# boardv1.net
KiCad netlist of a schematic drawn in EAGLE
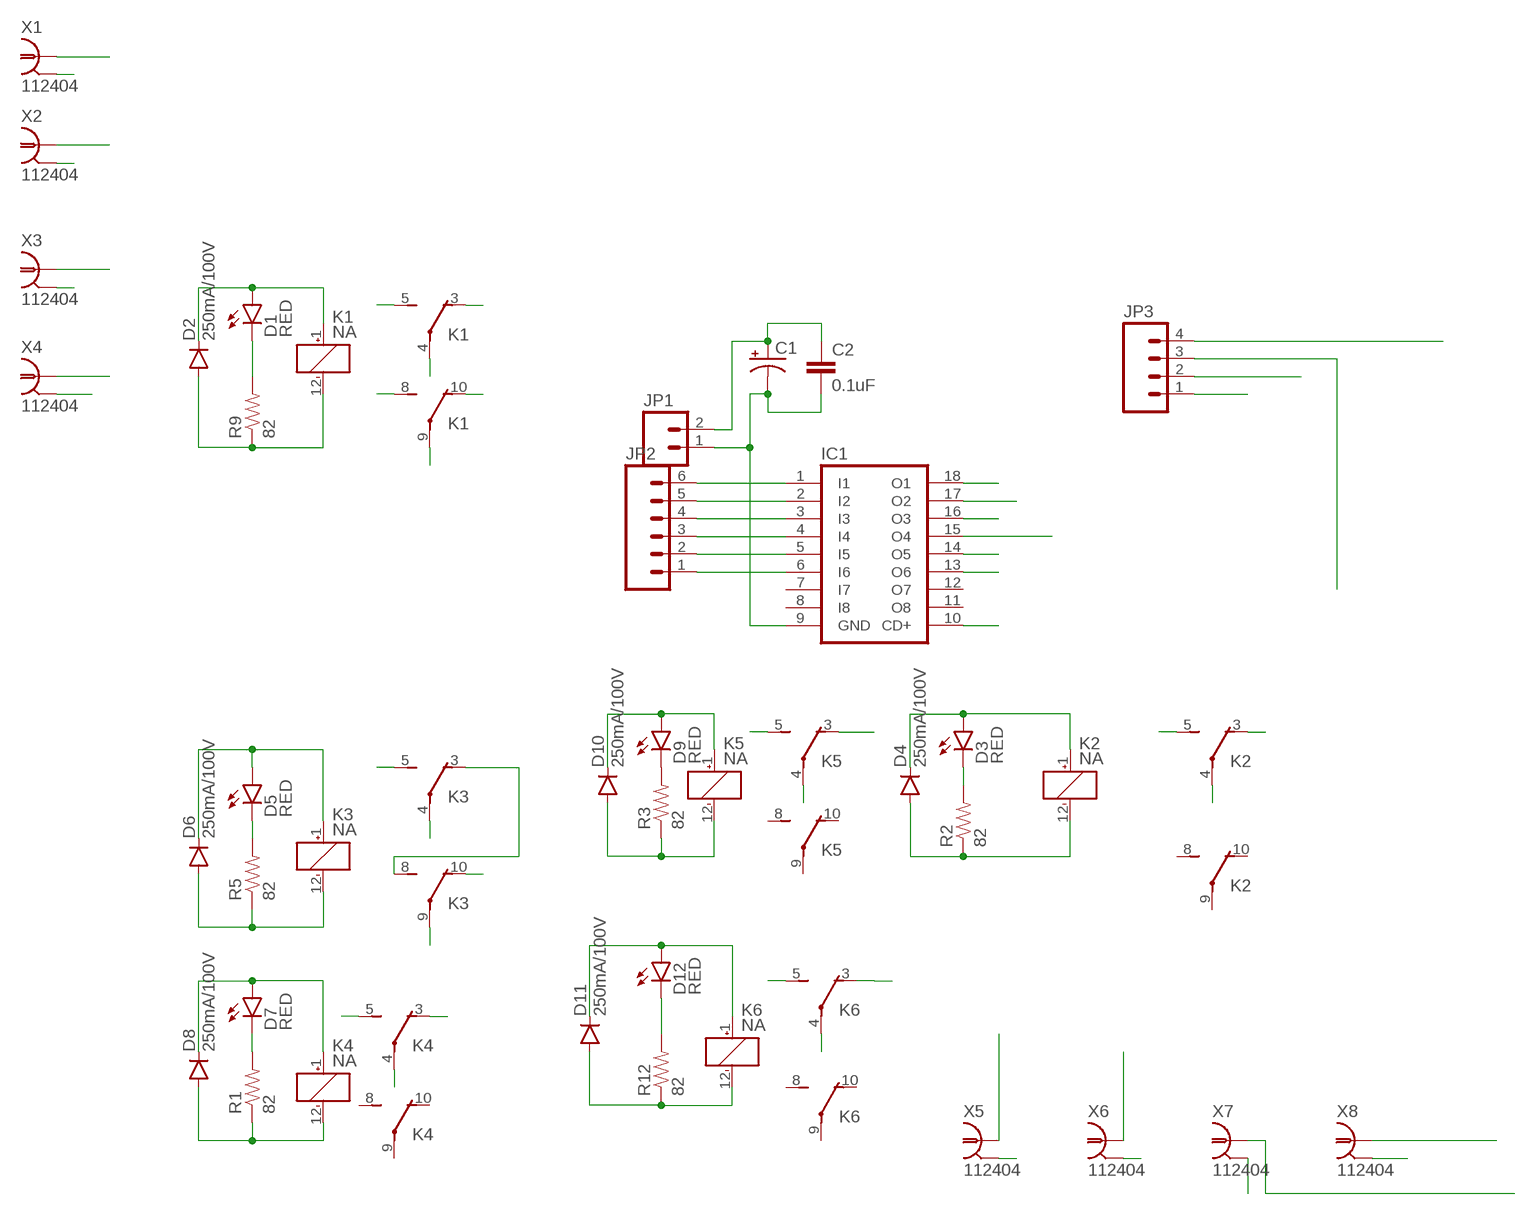
[diagram p0: schematic, sheet 1]

(export (version "E")
  (design (tool "Eeschema 10.0.6"))
  (components
    (comp (ref "C1")
      (value "100UF-25V-20%(PTH)")
      (footprint "eagle-import:CPOL-RADIAL-100UF-25V")
      (libsource (lib "eagle-import") (part "100UF-25V-20%(PTH)"))
    )
    (comp (ref "C2")
      (value "0.1uF")
      (footprint "eagle-import:0603-CAP")
      (libsource (lib "eagle-import") (part "0.1UF-25V-5%(0603)"))
    )
    (comp (ref "D1")
      (value "RED")
      (footprint "eagle-import:LED-1206")
      (libsource (lib "eagle-import") (part "LED-RED1206"))
    )
    (comp (ref "D2")
      (value "250mA/100V")
      (footprint "eagle-import:SOD-323")
      (libsource (lib "eagle-import") (part "DIODEBAS16"))
    )
    (comp (ref "D3")
      (value "RED")
      (footprint "eagle-import:LED-1206")
      (libsource (lib "eagle-import") (part "LED-RED1206"))
    )
    (comp (ref "D4")
      (value "250mA/100V")
      (footprint "eagle-import:SOD-323")
      (libsource (lib "eagle-import") (part "DIODEBAS16"))
    )
    (comp (ref "D5")
      (value "RED")
      (footprint "eagle-import:LED-1206")
      (libsource (lib "eagle-import") (part "LED-RED1206"))
    )
    (comp (ref "D6")
      (value "250mA/100V")
      (footprint "eagle-import:SOD-323")
      (libsource (lib "eagle-import") (part "DIODEBAS16"))
    )
    (comp (ref "D7")
      (value "RED")
      (footprint "eagle-import:LED-1206")
      (libsource (lib "eagle-import") (part "LED-RED1206"))
    )
    (comp (ref "D8")
      (value "250mA/100V")
      (footprint "eagle-import:SOD-323")
      (libsource (lib "eagle-import") (part "DIODEBAS16"))
    )
    (comp (ref "D9")
      (value "RED")
      (footprint "eagle-import:LED-1206")
      (libsource (lib "eagle-import") (part "LED-RED1206"))
    )
    (comp (ref "D10")
      (value "250mA/100V")
      (footprint "eagle-import:SOD-323")
      (libsource (lib "eagle-import") (part "DIODEBAS16"))
    )
    (comp (ref "D11")
      (value "250mA/100V")
      (footprint "eagle-import:SOD-323")
      (libsource (lib "eagle-import") (part "DIODEBAS16"))
    )
    (comp (ref "D12")
      (value "RED")
      (footprint "eagle-import:LED-1206")
      (libsource (lib "eagle-import") (part "LED-RED1206"))
    )
    (comp (ref "IC1")
      (value "ULN2803A")
      (footprint "eagle-import:DIL18")
      (libsource (lib "eagle-import") (part "ULN2803A"))
    )
    (comp (ref "JP1")
      (value "M02PTH")
      (footprint "eagle-import:1X02")
      (libsource (lib "eagle-import") (part "M02PTH"))
    )
    (comp (ref "JP2")
      (value "M06NO_SILK_YES_STOP")
      (footprint "eagle-import:1X06_NO_SILK_YES_STOP")
      (libsource (lib "eagle-import") (part "M06NO_SILK_YES_STOP"))
    )
    (comp (ref "JP3")
      (value "M04PTH")
      (footprint "eagle-import:1X04")
      (libsource (lib "eagle-import") (part "M04PTH"))
    )
    (comp (ref "K1") (value "NA") (footprint "eagle-import:NA") (libsource (lib "eagle-import") (part "NA")))
    (comp (ref "K2") (value "NA") (footprint "eagle-import:NA") (libsource (lib "eagle-import") (part "NA")))
    (comp (ref "K3") (value "NA") (footprint "eagle-import:NA") (libsource (lib "eagle-import") (part "NA")))
    (comp (ref "K4") (value "NA") (footprint "eagle-import:NA") (libsource (lib "eagle-import") (part "NA")))
    (comp (ref "K5") (value "NA") (footprint "eagle-import:NA") (libsource (lib "eagle-import") (part "NA")))
    (comp (ref "K6") (value "NA") (footprint "eagle-import:NA") (libsource (lib "eagle-import") (part "NA")))
    (comp (ref "R1")
      (value "82")
      (footprint "eagle-import:0603-RES")
      (libsource (lib "eagle-import") (part "82OHM-1/10W-1%(0603)SMD"))
    )
    (comp (ref "R2")
      (value "82")
      (footprint "eagle-import:0603-RES")
      (libsource (lib "eagle-import") (part "82OHM-1/10W-1%(0603)SMD"))
    )
    (comp (ref "R3")
      (value "82")
      (footprint "eagle-import:0603-RES")
      (libsource (lib "eagle-import") (part "82OHM-1/10W-1%(0603)SMD"))
    )
    (comp (ref "R5")
      (value "82")
      (footprint "eagle-import:0603-RES")
      (libsource (lib "eagle-import") (part "82OHM-1/10W-1%(0603)SMD"))
    )
    (comp (ref "R9")
      (value "82")
      (footprint "eagle-import:0603-RES")
      (libsource (lib "eagle-import") (part "82OHM-1/10W-1%(0603)SMD"))
    )
    (comp (ref "R12")
      (value "82")
      (footprint "eagle-import:0603-RES")
      (libsource (lib "eagle-import") (part "82OHM-1/10W-1%(0603)SMD"))
    )
    (comp (ref "X1")
      (value "112404")
      (footprint "eagle-import:112404")
      (fields (field (name "MF") "Amphenol Connex"))
      (libsource (lib "eagle-import") (part "112404"))
    )
    (comp (ref "X2")
      (value "112404")
      (footprint "eagle-import:112404")
      (fields (field (name "MF") "Amphenol Connex"))
      (libsource (lib "eagle-import") (part "112404"))
    )
    (comp (ref "X3")
      (value "112404")
      (footprint "eagle-import:112404")
      (fields (field (name "MF") "Amphenol Connex"))
      (libsource (lib "eagle-import") (part "112404"))
    )
    (comp (ref "X4")
      (value "112404")
      (footprint "eagle-import:112404")
      (fields (field (name "MF") "Amphenol Connex"))
      (libsource (lib "eagle-import") (part "112404"))
    )
    (comp (ref "X5")
      (value "112404")
      (footprint "eagle-import:112404")
      (fields (field (name "MF") "Amphenol Connex"))
      (libsource (lib "eagle-import") (part "112404"))
    )
    (comp (ref "X6")
      (value "112404")
      (footprint "eagle-import:112404")
      (fields (field (name "MF") "Amphenol Connex"))
      (libsource (lib "eagle-import") (part "112404"))
    )
    (comp (ref "X7")
      (value "112404")
      (footprint "eagle-import:112404")
      (fields (field (name "MF") "Amphenol Connex"))
      (libsource (lib "eagle-import") (part "112404"))
    )
    (comp (ref "X8")
      (value "112404")
      (footprint "eagle-import:112404")
      (fields (field (name "MF") "Amphenol Connex"))
      (libsource (lib "eagle-import") (part "112404"))
    )
  )
  (nets
    (net (code "1") (name "/ARDUINO1") (class "Default")
      (node (ref "JP3") (pin "4") (pinfunction "4_4") (pintype "passive"))
      (node (ref "K2") (pin "3") (pinfunction "O_3") (pintype "passive"))
    )
    (net (code "2") (name "/ARDUINO2") (class "Default")
      (node (ref "JP3") (pin "3") (pinfunction "3_3") (pintype "passive"))
      (node (ref "K6") (pin "3") (pinfunction "O_3") (pintype "passive"))
    )
    (net (code "3") (name "/ARDUINO3") (class "Default")
      (node (ref "JP3") (pin "2") (pinfunction "2_2") (pintype "passive"))
      (node (ref "K5") (pin "3") (pinfunction "O_3") (pintype "passive"))
    )
    (net (code "4") (name "/ARDUINO4") (class "Default")
      (node (ref "JP3") (pin "1") (pinfunction "1_1") (pintype "passive"))
      (node (ref "K4") (pin "3") (pinfunction "O_3") (pintype "passive"))
    )
    (net (code "5") (name "/GND") (class "Default")
      (node (ref "X1") (pin "2") (pinfunction "2_2") (pintype "passive"))
      (node (ref "X1") (pin "3") (pinfunction "2_3") (pintype "passive"))
      (node (ref "X1") (pin "4") (pinfunction "2_4") (pintype "passive"))
      (node (ref "X1") (pin "5") (pinfunction "2_5") (pintype "passive"))
      (node (ref "X2") (pin "2") (pinfunction "2_2") (pintype "passive"))
      (node (ref "X2") (pin "3") (pinfunction "2_3") (pintype "passive"))
      (node (ref "X2") (pin "4") (pinfunction "2_4") (pintype "passive"))
      (node (ref "X2") (pin "5") (pinfunction "2_5") (pintype "passive"))
      (node (ref "X3") (pin "2") (pinfunction "2_2") (pintype "passive"))
      (node (ref "X3") (pin "3") (pinfunction "2_3") (pintype "passive"))
      (node (ref "X3") (pin "4") (pinfunction "2_4") (pintype "passive"))
      (node (ref "X3") (pin "5") (pinfunction "2_5") (pintype "passive"))
      (node (ref "X4") (pin "2") (pinfunction "2_2") (pintype "passive"))
      (node (ref "X4") (pin "3") (pinfunction "2_3") (pintype "passive"))
      (node (ref "X4") (pin "4") (pinfunction "2_4") (pintype "passive"))
      (node (ref "X4") (pin "5") (pinfunction "2_5") (pintype "passive"))
      (node (ref "X5") (pin "2") (pinfunction "2_2") (pintype "passive"))
      (node (ref "X5") (pin "3") (pinfunction "2_3") (pintype "passive"))
      (node (ref "X5") (pin "4") (pinfunction "2_4") (pintype "passive"))
      (node (ref "X5") (pin "5") (pinfunction "2_5") (pintype "passive"))
      (node (ref "X6") (pin "2") (pinfunction "2_2") (pintype "passive"))
      (node (ref "X6") (pin "3") (pinfunction "2_3") (pintype "passive"))
      (node (ref "X6") (pin "4") (pinfunction "2_4") (pintype "passive"))
      (node (ref "X6") (pin "5") (pinfunction "2_5") (pintype "passive"))
      (node (ref "X7") (pin "2") (pinfunction "2_2") (pintype "passive"))
      (node (ref "X7") (pin "3") (pinfunction "2_3") (pintype "passive"))
      (node (ref "X7") (pin "4") (pinfunction "2_4") (pintype "passive"))
      (node (ref "X7") (pin "5") (pinfunction "2_5") (pintype "passive"))
      (node (ref "X8") (pin "2") (pinfunction "2_2") (pintype "passive"))
      (node (ref "X8") (pin "3") (pinfunction "2_3") (pintype "passive"))
      (node (ref "X8") (pin "4") (pinfunction "2_4") (pintype "passive"))
      (node (ref "X8") (pin "5") (pinfunction "2_5") (pintype "passive"))
    )
    (net (code "6") (name "/INPUTA") (class "Default")
      (node (ref "K1") (pin "4") (pinfunction "P_4") (pintype "passive"))
      (node (ref "X1") (pin "1") (pinfunction "1_1") (pintype "passive"))
    )
    (net (code "7") (name "/INPUTB") (class "Default")
      (node (ref "K1") (pin "9") (pinfunction "P_9") (pintype "passive"))
      (node (ref "X2") (pin "1") (pinfunction "1_1") (pintype "passive"))
    )
    (net (code "8") (name "/OUTPUT1") (class "Default")
      (node (ref "K4") (pin "4") (pinfunction "P_4") (pintype "passive"))
      (node (ref "X5") (pin "1") (pinfunction "1_1") (pintype "passive"))
    )
    (net (code "9") (name "/OUTPUT2") (class "Default")
      (node (ref "K5") (pin "4") (pinfunction "P_4") (pintype "passive"))
      (node (ref "X6") (pin "1") (pinfunction "1_1") (pintype "passive"))
    )
    (net (code "10") (name "/OUTPUT3") (class "Default")
      (node (ref "K6") (pin "4") (pinfunction "P_4") (pintype "passive"))
      (node (ref "X7") (pin "1") (pinfunction "1_1") (pintype "passive"))
    )
    (net (code "11") (name "/OUTPUT4") (class "Default")
      (node (ref "K2") (pin "4") (pinfunction "P_4") (pintype "passive"))
      (node (ref "X8") (pin "1") (pinfunction "1_1") (pintype "passive"))
    )
    (net (code "12") (name "/OUTPUTA") (class "Default")
      (node (ref "K1") (pin "3") (pinfunction "O_3") (pintype "passive"))
      (node (ref "K3") (pin "5") (pinfunction "S_5") (pintype "passive"))
      (node (ref "X3") (pin "1") (pinfunction "1_1") (pintype "passive"))
    )
    (net (code "13") (name "/OUTPUTB") (class "Default")
      (node (ref "K1") (pin "10") (pinfunction "O_10") (pintype "passive"))
      (node (ref "K3") (pin "10") (pinfunction "O_10") (pintype "passive"))
      (node (ref "X4") (pin "1") (pinfunction "1_1") (pintype "passive"))
    )
    (net (code "14") (name "/R1") (class "Default")
      (node (ref "D4") (pin "A") (pinfunction "A_A") (pintype "passive"))
      (node (ref "IC1") (pin "18") (pinfunction "O1_18") (pintype "open_collector"))
      (node (ref "K2") (pin "12") (pinfunction "-_12") (pintype "passive"))
      (node (ref "R2") (pin "1") (pinfunction "1_1") (pintype "passive"))
    )
    (net (code "15") (name "/R2") (class "Default")
      (node (ref "D11") (pin "A") (pinfunction "A_A") (pintype "passive"))
      (node (ref "IC1") (pin "17") (pinfunction "O2_17") (pintype "open_collector"))
      (node (ref "K6") (pin "12") (pinfunction "-_12") (pintype "passive"))
      (node (ref "R12") (pin "1") (pinfunction "1_1") (pintype "passive"))
    )
    (net (code "16") (name "/R3") (class "Default")
      (node (ref "D10") (pin "A") (pinfunction "A_A") (pintype "passive"))
      (node (ref "IC1") (pin "16") (pinfunction "O3_16") (pintype "open_collector"))
      (node (ref "K5") (pin "12") (pinfunction "-_12") (pintype "passive"))
      (node (ref "R3") (pin "1") (pinfunction "1_1") (pintype "passive"))
    )
    (net (code "17") (name "/R4") (class "Default")
      (node (ref "D8") (pin "A") (pinfunction "A_A") (pintype "passive"))
      (node (ref "IC1") (pin "15") (pinfunction "O4_15") (pintype "open_collector"))
      (node (ref "K4") (pin "12") (pinfunction "-_12") (pintype "passive"))
      (node (ref "R1") (pin "1") (pinfunction "1_1") (pintype "passive"))
    )
    (net (code "18") (name "/R5") (class "Default")
      (node (ref "D6") (pin "A") (pinfunction "A_A") (pintype "passive"))
      (node (ref "IC1") (pin "14") (pinfunction "O5_14") (pintype "open_collector"))
      (node (ref "K3") (pin "12") (pinfunction "-_12") (pintype "passive"))
      (node (ref "R5") (pin "1") (pinfunction "1_1") (pintype "passive"))
    )
    (net (code "19") (name "/R6") (class "Default")
      (node (ref "D2") (pin "A") (pinfunction "A_A") (pintype "passive"))
      (node (ref "IC1") (pin "13") (pinfunction "O6_13") (pintype "open_collector"))
      (node (ref "K1") (pin "12") (pinfunction "-_12") (pintype "passive"))
      (node (ref "R9") (pin "1") (pinfunction "1_1") (pintype "passive"))
    )
    (net (code "20") (name "/SIG3A") (class "Default")
      (node (ref "K1") (pin "5") (pinfunction "S_5") (pintype "passive"))
      (node (ref "K3") (pin "4") (pinfunction "P_4") (pintype "passive"))
    )
    (net (code "21") (name "/SIG3B") (class "Default")
      (node (ref "K1") (pin "8") (pinfunction "S_8") (pintype "passive"))
      (node (ref "K3") (pin "9") (pinfunction "P_9") (pintype "passive"))
    )
    (net (code "22") (name "/SIG4A") (class "Default")
      (node (ref "K2") (pin "5") (pinfunction "S_5") (pintype "passive"))
      (node (ref "K3") (pin "3") (pinfunction "O_3") (pintype "passive"))
      (node (ref "K3") (pin "8") (pinfunction "S_8") (pintype "passive"))
      (node (ref "K4") (pin "5") (pinfunction "S_5") (pintype "passive"))
      (node (ref "K5") (pin "5") (pinfunction "S_5") (pintype "passive"))
      (node (ref "K6") (pin "5") (pinfunction "S_5") (pintype "passive"))
    )
    (net (code "23") (name "/VCC") (class "Default")
      (node (ref "C1") (pin "1") (pinfunction "+_1") (pintype "passive"))
      (node (ref "C2") (pin "1") (pinfunction "1_1") (pintype "passive"))
      (node (ref "D1") (pin "A") (pinfunction "A_A") (pintype "passive"))
      (node (ref "D10") (pin "C") (pinfunction "C_C") (pintype "passive"))
      (node (ref "D11") (pin "C") (pinfunction "C_C") (pintype "passive"))
      (node (ref "D12") (pin "A") (pinfunction "A_A") (pintype "passive"))
      (node (ref "D2") (pin "C") (pinfunction "C_C") (pintype "passive"))
      (node (ref "D3") (pin "A") (pinfunction "A_A") (pintype "passive"))
      (node (ref "D4") (pin "C") (pinfunction "C_C") (pintype "passive"))
      (node (ref "D5") (pin "A") (pinfunction "A_A") (pintype "passive"))
      (node (ref "D6") (pin "C") (pinfunction "C_C") (pintype "passive"))
      (node (ref "D7") (pin "A") (pinfunction "A_A") (pintype "passive"))
      (node (ref "D8") (pin "C") (pinfunction "C_C") (pintype "passive"))
      (node (ref "D9") (pin "A") (pinfunction "A_A") (pintype "passive"))
      (node (ref "IC1") (pin "10") (pinfunction "CD+_10") (pintype "passive"))
      (node (ref "JP1") (pin "2") (pinfunction "2_2") (pintype "passive"))
      (node (ref "K1") (pin "1") (pinfunction "+_1") (pintype "passive"))
      (node (ref "K2") (pin "1") (pinfunction "+_1") (pintype "passive"))
      (node (ref "K3") (pin "1") (pinfunction "+_1") (pintype "passive"))
      (node (ref "K4") (pin "1") (pinfunction "+_1") (pintype "passive"))
      (node (ref "K5") (pin "1") (pinfunction "+_1") (pintype "passive"))
      (node (ref "K6") (pin "1") (pinfunction "+_1") (pintype "passive"))
    )
    (net (code "24") (name "Net-(C1--)") (class "Default")
      (node (ref "C1") (pin "2") (pinfunction "-_2") (pintype "passive"))
      (node (ref "C2") (pin "2") (pinfunction "2_2") (pintype "passive"))
      (node (ref "IC1") (pin "9") (pinfunction "GND_9") (pintype "power_in"))
      (node (ref "JP1") (pin "1") (pinfunction "1_1") (pintype "passive"))
    )
    (net (code "25") (name "Net-(D1-PadC)") (class "Default")
      (node (ref "D1") (pin "C") (pinfunction "C_C") (pintype "passive"))
      (node (ref "R9") (pin "2") (pinfunction "2_2") (pintype "passive"))
    )
    (net (code "26") (name "Net-(D3-PadC)") (class "Default")
      (node (ref "D3") (pin "C") (pinfunction "C_C") (pintype "passive"))
      (node (ref "R2") (pin "2") (pinfunction "2_2") (pintype "passive"))
    )
    (net (code "27") (name "Net-(D5-PadC)") (class "Default")
      (node (ref "D5") (pin "C") (pinfunction "C_C") (pintype "passive"))
      (node (ref "R5") (pin "2") (pinfunction "2_2") (pintype "passive"))
    )
    (net (code "28") (name "Net-(D7-PadC)") (class "Default")
      (node (ref "D7") (pin "C") (pinfunction "C_C") (pintype "passive"))
      (node (ref "R1") (pin "2") (pinfunction "2_2") (pintype "passive"))
    )
    (net (code "29") (name "Net-(D9-PadC)") (class "Default")
      (node (ref "D9") (pin "C") (pinfunction "C_C") (pintype "passive"))
      (node (ref "R3") (pin "2") (pinfunction "2_2") (pintype "passive"))
    )
    (net (code "30") (name "Net-(D12-PadC)") (class "Default")
      (node (ref "D12") (pin "C") (pinfunction "C_C") (pintype "passive"))
      (node (ref "R12") (pin "2") (pinfunction "2_2") (pintype "passive"))
    )
    (net (code "31") (name "Net-(IC1-I1)") (class "Default")
      (node (ref "IC1") (pin "1") (pinfunction "I1_1") (pintype "input"))
      (node (ref "JP2") (pin "6") (pinfunction "6_6") (pintype "passive"))
    )
    (net (code "32") (name "Net-(IC1-I2)") (class "Default")
      (node (ref "IC1") (pin "2") (pinfunction "I2_2") (pintype "input"))
      (node (ref "JP2") (pin "5") (pinfunction "5_5") (pintype "passive"))
    )
    (net (code "33") (name "Net-(IC1-I3)") (class "Default")
      (node (ref "IC1") (pin "3") (pinfunction "I3_3") (pintype "input"))
      (node (ref "JP2") (pin "4") (pinfunction "4_4") (pintype "passive"))
    )
    (net (code "34") (name "Net-(IC1-I4)") (class "Default")
      (node (ref "IC1") (pin "4") (pinfunction "I4_4") (pintype "input"))
      (node (ref "JP2") (pin "3") (pinfunction "3_3") (pintype "passive"))
    )
    (net (code "35") (name "Net-(IC1-I5)") (class "Default")
      (node (ref "IC1") (pin "5") (pinfunction "I5_5") (pintype "input"))
      (node (ref "JP2") (pin "2") (pinfunction "2_2") (pintype "passive"))
    )
    (net (code "36") (name "Net-(IC1-I6)") (class "Default")
      (node (ref "IC1") (pin "6") (pinfunction "I6_6") (pintype "input"))
      (node (ref "JP2") (pin "1") (pinfunction "1_1") (pintype "passive"))
    )
    (net (code "37") (name "unconnected-(IC1-I7-Pad7)") (class "Default")
      (node (ref "IC1") (pin "7") (pinfunction "I7_7") (pintype "input"))
    )
    (net (code "38") (name "unconnected-(IC1-I8-Pad8)") (class "Default")
      (node (ref "IC1") (pin "8") (pinfunction "I8_8") (pintype "input"))
    )
    (net (code "39") (name "unconnected-(IC1-O7-Pad12)") (class "Default")
      (node (ref "IC1") (pin "12") (pinfunction "O7_12") (pintype "open_collector"))
    )
    (net (code "40") (name "unconnected-(IC1-O8-Pad11)") (class "Default")
      (node (ref "IC1") (pin "11") (pinfunction "O8_11") (pintype "open_collector"))
    )
    (net (code "41") (name "unconnected-(K2C-O-Pad10)") (class "Default")
      (node (ref "K2") (pin "10") (pinfunction "O_10") (pintype "passive"))
    )
    (net (code "42") (name "unconnected-(K2C-P-Pad9)") (class "Default")
      (node (ref "K2") (pin "9") (pinfunction "P_9") (pintype "passive"))
    )
    (net (code "43") (name "unconnected-(K2C-S-Pad8)") (class "Default")
      (node (ref "K2") (pin "8") (pinfunction "S_8") (pintype "passive"))
    )
    (net (code "44") (name "unconnected-(K4C-O-Pad10)") (class "Default")
      (node (ref "K4") (pin "10") (pinfunction "O_10") (pintype "passive"))
    )
    (net (code "45") (name "unconnected-(K4C-P-Pad9)") (class "Default")
      (node (ref "K4") (pin "9") (pinfunction "P_9") (pintype "passive"))
    )
    (net (code "46") (name "unconnected-(K4C-S-Pad8)") (class "Default")
      (node (ref "K4") (pin "8") (pinfunction "S_8") (pintype "passive"))
    )
    (net (code "47") (name "unconnected-(K5C-O-Pad10)") (class "Default")
      (node (ref "K5") (pin "10") (pinfunction "O_10") (pintype "passive"))
    )
    (net (code "48") (name "unconnected-(K5C-P-Pad9)") (class "Default")
      (node (ref "K5") (pin "9") (pinfunction "P_9") (pintype "passive"))
    )
    (net (code "49") (name "unconnected-(K5C-S-Pad8)") (class "Default")
      (node (ref "K5") (pin "8") (pinfunction "S_8") (pintype "passive"))
    )
    (net (code "50") (name "unconnected-(K6C-O-Pad10)") (class "Default")
      (node (ref "K6") (pin "10") (pinfunction "O_10") (pintype "passive"))
    )
    (net (code "51") (name "unconnected-(K6C-P-Pad9)") (class "Default")
      (node (ref "K6") (pin "9") (pinfunction "P_9") (pintype "passive"))
    )
    (net (code "52") (name "unconnected-(K6C-S-Pad8)") (class "Default")
      (node (ref "K6") (pin "8") (pinfunction "S_8") (pintype "passive"))
    )
  )
)
